# E1AA60D5.net
KiCad netlist of a schematic drawn in EAGLE
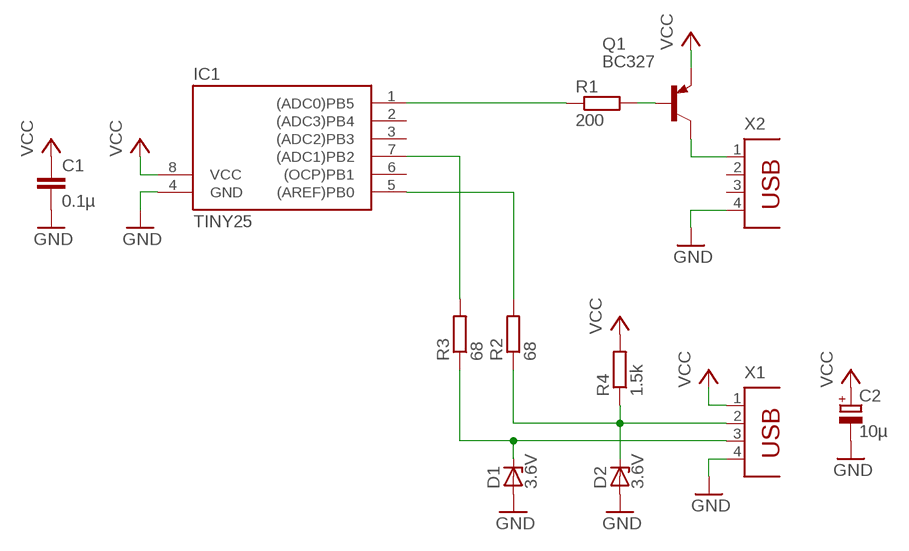
[diagram p0: schematic, sheet 1]

(export (version "E")
  (design (tool "Eeschema 10.0.6"))
  (components
    (comp (ref "C1")
      (value "0.1µ")
      (footprint "eagle-import:C025-025X050")
      (libsource (lib "eagle-import") (part "C-EU025-025X050"))
    )
    (comp (ref "C2")
      (value "10µ")
      (footprint "eagle-import:E2,5-6")
      (libsource (lib "eagle-import") (part "CPOL-EUE2.5-6"))
    )
    (comp (ref "D1")
      (value "3.6V")
      (footprint "eagle-import:DO35Z10")
      (libsource (lib "eagle-import") (part "ZENER-DIODEDO35Z10"))
    )
    (comp (ref "D2")
      (value "3.6V")
      (footprint "eagle-import:DO35Z10")
      (libsource (lib "eagle-import") (part "ZENER-DIODEDO35Z10"))
    )
    (comp (ref "IC1")
      (value "TINY25")
      (footprint "eagle-import:DIL08")
      (libsource (lib "eagle-import") (part "TINY15LP"))
    )
    (comp (ref "Q1")
      (value "BC327")
      (footprint "eagle-import:TO92-EBC")
      (libsource (lib "eagle-import") (part "BC327"))
    )
    (comp (ref "R1")
      (value "200")
      (footprint "eagle-import:0207_10")
      (libsource (lib "eagle-import") (part "R-EU_0207/10"))
    )
    (comp (ref "R2")
      (value "68")
      (footprint "eagle-import:0207_10")
      (libsource (lib "eagle-import") (part "R-EU_0207/10"))
    )
    (comp (ref "R3")
      (value "68")
      (footprint "eagle-import:0207_10")
      (libsource (lib "eagle-import") (part "R-EU_0207/10"))
    )
    (comp (ref "R4")
      (value "1.5k")
      (footprint "eagle-import:0207_10")
      (libsource (lib "eagle-import") (part "R-EU_0207/10"))
    )
    (comp (ref "X1")
      (value "PN87520")
      (footprint "eagle-import:PN87520")
      (libsource (lib "eagle-import") (part "PN87520"))
    )
    (comp (ref "X2")
      (value "PN87520")
      (footprint "eagle-import:PN87520")
      (libsource (lib "eagle-import") (part "PN87520"))
    )
  )
  (nets
    (net (code "1") (name "GND") (class "Default")
      (node (ref "C1") (pin "2") (pinfunction "2_2") (pintype "passive"))
      (node (ref "C2") (pin "-") (pinfunction "-_-") (pintype "passive"))
      (node (ref "D1") (pin "A") (pinfunction "A_A") (pintype "passive"))
      (node (ref "D2") (pin "A") (pinfunction "A_A") (pintype "passive"))
      (node (ref "IC1") (pin "4") (pinfunction "GND_4") (pintype "power_in"))
      (node (ref "X1") (pin "4") (pinfunction "4_4") (pintype "passive"))
      (node (ref "X2") (pin "4") (pinfunction "4_4") (pintype "passive"))
    )
    (net (code "2") (name "Net-(D1-PadC)") (class "Default")
      (node (ref "D1") (pin "C") (pinfunction "C_C") (pintype "passive"))
      (node (ref "R3") (pin "1") (pinfunction "1_1") (pintype "passive"))
      (node (ref "X1") (pin "3") (pinfunction "3_3") (pintype "passive"))
    )
    (net (code "3") (name "Net-(D2-PadC)") (class "Default")
      (node (ref "D2") (pin "C") (pinfunction "C_C") (pintype "passive"))
      (node (ref "R2") (pin "1") (pinfunction "1_1") (pintype "passive"))
      (node (ref "R4") (pin "1") (pinfunction "1_1") (pintype "passive"))
      (node (ref "X1") (pin "2") (pinfunction "2_2") (pintype "passive"))
    )
    (net (code "4") (name "Net-(IC1-(ADC0)PB5)") (class "Default")
      (node (ref "IC1") (pin "1") (pinfunction "(ADC0)PB5_1") (pintype "bidirectional"))
      (node (ref "R1") (pin "1") (pinfunction "1_1") (pintype "passive"))
    )
    (net (code "5") (name "Net-(IC1-(ADC1)PB2)") (class "Default")
      (node (ref "IC1") (pin "7") (pinfunction "(ADC1)PB2_7") (pintype "bidirectional"))
      (node (ref "R3") (pin "2") (pinfunction "2_2") (pintype "passive"))
    )
    (net (code "6") (name "Net-(IC1-(AREF)PB0)") (class "Default")
      (node (ref "IC1") (pin "5") (pinfunction "(AREF)PB0_5") (pintype "bidirectional"))
      (node (ref "R2") (pin "2") (pinfunction "2_2") (pintype "passive"))
    )
    (net (code "7") (name "Net-(Q1-PadB)") (class "Default")
      (node (ref "Q1") (pin "B") (pinfunction "B_B") (pintype "passive"))
      (node (ref "R1") (pin "2") (pinfunction "2_2") (pintype "passive"))
    )
    (net (code "8") (name "Net-(Q1-PadC)") (class "Default")
      (node (ref "Q1") (pin "C") (pinfunction "C_C") (pintype "passive"))
      (node (ref "X2") (pin "1") (pinfunction "1_1") (pintype "passive"))
    )
    (net (code "9") (name "VCC") (class "Default")
      (node (ref "C1") (pin "1") (pinfunction "1_1") (pintype "passive"))
      (node (ref "C2") (pin "+") (pinfunction "+_+") (pintype "passive"))
      (node (ref "IC1") (pin "8") (pinfunction "VCC_8") (pintype "power_in"))
      (node (ref "Q1") (pin "E") (pinfunction "E_E") (pintype "passive"))
      (node (ref "R4") (pin "2") (pinfunction "2_2") (pintype "passive"))
      (node (ref "X1") (pin "1") (pinfunction "1_1") (pintype "passive"))
    )
    (net (code "10") (name "unconnected-(IC1-(ADC2)PB3-Pad3)") (class "Default")
      (node (ref "IC1") (pin "3") (pinfunction "(ADC2)PB3_3") (pintype "bidirectional"))
    )
    (net (code "11") (name "unconnected-(IC1-(ADC3)PB4-Pad2)") (class "Default")
      (node (ref "IC1") (pin "2") (pinfunction "(ADC3)PB4_2") (pintype "bidirectional"))
    )
    (net (code "12") (name "unconnected-(IC1-(OCP)PB1-Pad6)") (class "Default")
      (node (ref "IC1") (pin "6") (pinfunction "(OCP)PB1_6") (pintype "bidirectional"))
    )
    (net (code "13") (name "unconnected-(X2-Pad2)") (class "Default")
      (node (ref "X2") (pin "2") (pinfunction "2_2") (pintype "passive"))
    )
    (net (code "14") (name "unconnected-(X2-Pad3)") (class "Default")
      (node (ref "X2") (pin "3") (pinfunction "3_3") (pintype "passive"))
    )
  )
)
